# ProProject_MiSTeR_SNAC_Sega_Saturn_2024-.net
KiCad netlist of a schematic drawn in EasyEDA Pro
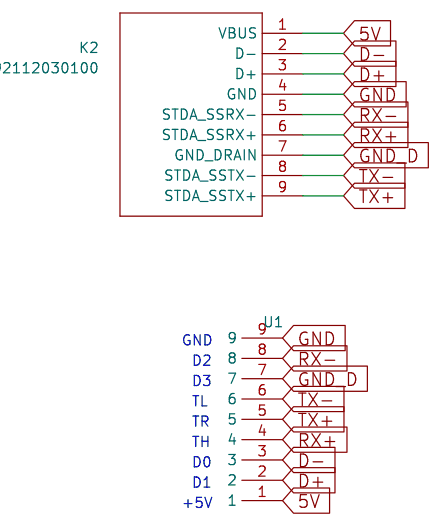
[diagram p0: schematic sheet]

(export (version "E")
  (design (tool "Eeschema 10.0.6"))
  (components
    (comp (ref "K2")
      (value "692112030100")
      (footprint "easyedapro:692112030100")
      (libsource (lib "easyedapro") (part "Wuerth_Elektronik_eiCan_Communication_Connectors_STENCIL_692112030100_"))
    )
    (comp (ref "U1")
      (value "~")
      (footprint "easyedapro:SATURN CONNECTOR")
      (libsource (lib "easyedapro") (part "saturn_connector"))
    )
  )
  (nets
    (net (code "1") (name "5V") (class "Default")
      (node (ref "K2") (pin "1") (pinfunction "VBUS_1") (pintype "bidirectional"))
      (node (ref "U1") (pin "1") (pinfunction "1_1") (pintype "input"))
    )
    (net (code "2") (name "D+") (class "Default")
      (node (ref "K2") (pin "3") (pinfunction "D+_3") (pintype "bidirectional"))
      (node (ref "U1") (pin "2") (pinfunction "2_2") (pintype "input"))
    )
    (net (code "3") (name "D-") (class "Default")
      (node (ref "K2") (pin "2") (pinfunction "D-_2") (pintype "bidirectional"))
      (node (ref "U1") (pin "3") (pinfunction "3_3") (pintype "input"))
    )
    (net (code "4") (name "GND") (class "Default")
      (node (ref "K2") (pin "4") (pinfunction "GND_4") (pintype "bidirectional"))
      (node (ref "U1") (pin "9") (pinfunction "9_9") (pintype "input"))
    )
    (net (code "5") (name "GND_D") (class "Default")
      (node (ref "K2") (pin "7") (pinfunction "GND_DRAIN_7") (pintype "bidirectional"))
      (node (ref "U1") (pin "7") (pinfunction "7_7") (pintype "input"))
    )
    (net (code "6") (name "RX+") (class "Default")
      (node (ref "K2") (pin "6") (pinfunction "STDA_SSRX+_6") (pintype "bidirectional"))
      (node (ref "U1") (pin "4") (pinfunction "4_4") (pintype "input"))
    )
    (net (code "7") (name "RX-") (class "Default")
      (node (ref "K2") (pin "5") (pinfunction "STDA_SSRX-_5") (pintype "bidirectional"))
      (node (ref "U1") (pin "8") (pinfunction "8_8") (pintype "input"))
    )
    (net (code "8") (name "TX+") (class "Default")
      (node (ref "K2") (pin "9") (pinfunction "STDA_SSTX+_9") (pintype "bidirectional"))
      (node (ref "U1") (pin "5") (pinfunction "5_5") (pintype "input"))
    )
    (net (code "9") (name "TX-") (class "Default")
      (node (ref "K2") (pin "8") (pinfunction "STDA_SSTX-_8") (pintype "bidirectional"))
      (node (ref "U1") (pin "6") (pinfunction "6_6") (pintype "input"))
    )
  )
)
